# SB_Motor_Driver_Module.net
KiCad netlist of a schematic drawn in Altium Designer
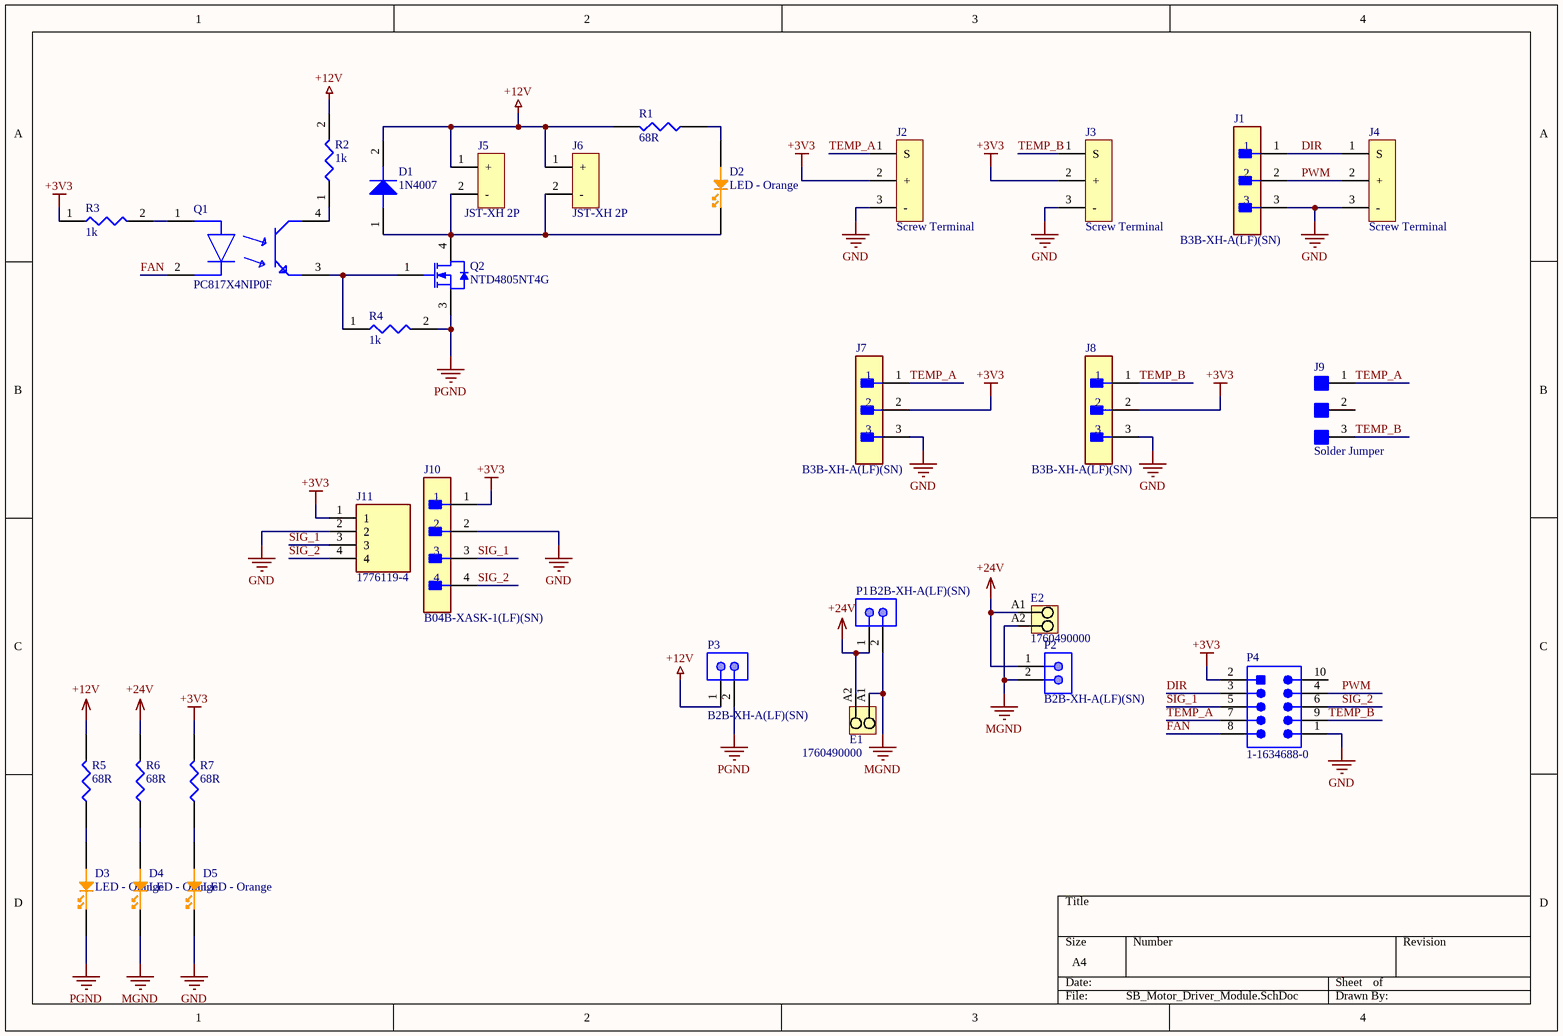
[diagram p0: SB_Motor_Driver_Module.SchDoc]

(export (version "E")
  (design (tool "Eeschema 10.0.6"))
  (components
    (comp (ref "D1")
      (value "1N4007")
      (footprint "M7 1N4007 SMA")
      (description "1000V 1A Rectifier")
      (fields
        (field (name "MANUFACTURER") "Sangdest Microelectronics")
        (field (name "MANUFACTURER PART NUMBER") "1N4007FLTR")
      )
      (libsource (lib "SectionE_BreakOut") (part "1N4007FLTR"))
    )
    (comp (ref "D2")
      (value "LED - Orange")
      (footprint "LED0603-Orange")
      (description "LED ORANGE CLEAR SMD")
      (fields
        (field (name "MANUFACTURER") "Vishay Lite-On")
        (field (name "MANUFACTURER PART NUMBER") "LTST-C191KFKT")
      )
      (libsource (lib "SectionE_BreakOut") (part "LTST-C191KFKT"))
    )
    (comp (ref "D3")
      (value "LED - Orange")
      (footprint "LED0603-Orange")
      (description "LED ORANGE CLEAR SMD")
      (fields
        (field (name "MANUFACTURER") "Vishay Lite-On")
        (field (name "MANUFACTURER PART NUMBER") "LTST-C191KFKT")
      )
      (libsource (lib "SectionE_BreakOut") (part "LTST-C191KFKT"))
    )
    (comp (ref "D4")
      (value "LED - Orange")
      (footprint "LED0603-Orange")
      (description "LED ORANGE CLEAR SMD")
      (fields
        (field (name "MANUFACTURER") "Vishay Lite-On")
        (field (name "MANUFACTURER PART NUMBER") "LTST-C191KFKT")
      )
      (libsource (lib "SectionE_BreakOut") (part "LTST-C191KFKT"))
    )
    (comp (ref "D5")
      (value "LED - Orange")
      (footprint "LED0603-Orange")
      (description "LED ORANGE CLEAR SMD")
      (fields
        (field (name "MANUFACTURER") "Vishay Lite-On")
        (field (name "MANUFACTURER PART NUMBER") "LTST-C191KFKT")
      )
      (libsource (lib "SectionE_BreakOut") (part "LTST-C191KFKT"))
    )
    (comp (ref "E1")
      (value "1760490000")
      (footprint "PM_5_08_90_02")
      (description "OMNIMATE Signal - series PM")
      (fields (field (name "MANUFACTURER") "Weidmueller"))
      (libsource (lib "") (part "Terminal_02_1x02_1"))
    )
    (comp (ref "E2")
      (value "1760490000")
      (footprint "PM_5_08_90_02")
      (description "OMNIMATE Signal - series PM")
      (fields (field (name "MANUFACTURER") "Weidmueller"))
      (libsource (lib "Altium Content Vault") (part "Terminal_02_1x02"))
    )
    (comp (ref "J1")
      (value "B3B-XH-A(LF)(SN)")
      (footprint "FP-B3B-XH-A_LF_SN-MFG")
      (description "CONN HEADER VERT 3POS 2.5MM")
      (fields
        (field (name "OCTOPART") "https://octopart.com/b3b-xh-a%28lf%29%28sn%29-jst-3990185")
        (field (name "MANUFACTURER") "JST")
      )
      (libsource (lib "Altium Content Vault") (part "0d3f023dd272f625e17a2be33dea85f"))
    )
    (comp (ref "J2")
      (value "Screw Terminal")
      (footprint "Screw Terminal 3P 5.08MM")
      (description "TERM BLK 3P SIDE ENT 5.08MM PCB")
      (fields
        (field (name "MANUFACTURER") "On-Shore Technology")
        (field (name "MANUFACTURER PART NUMBER") "OSTTC032162")
      )
      (libsource (lib "SectionE_BreakOut") (part "OSTTC032162"))
    )
    (comp (ref "J3")
      (value "Screw Terminal")
      (footprint "Screw Terminal 3P 5.08MM")
      (description "TERM BLK 3P SIDE ENT 5.08MM PCB")
      (fields
        (field (name "MANUFACTURER") "On-Shore Technology")
        (field (name "MANUFACTURER PART NUMBER") "OSTTC032162")
      )
      (libsource (lib "SectionE_BreakOut") (part "OSTTC032162"))
    )
    (comp (ref "J4")
      (value "Screw Terminal")
      (footprint "Screw Terminal 3P 5.08MM")
      (description "TERM BLK 3P SIDE ENT 5.08MM PCB")
      (fields
        (field (name "MANUFACTURER") "On-Shore Technology")
        (field (name "MANUFACTURER PART NUMBER") "OSTTC032162")
      )
      (libsource (lib "SectionE_BreakOut") (part "OSTTC032162"))
    )
    (comp (ref "J5")
      (value "JST-XH 2P")
      (footprint "JST-XH 2P")
      (description "JST-XH 2 POS 2.5mm Solder ST Thru-Hole Box")
      (fields
        (field (name "MANUFACTURER") "JST")
        (field (name "MANUFACTURER PART NUMBER") "B2B-XH-A(LF)(SN)")
      )
      (libsource (lib "SectionE_BreakOut") (part "B2B-XH-A(LF)(SN)"))
    )
    (comp (ref "J6")
      (value "JST-XH 2P")
      (footprint "JST-XH 2P")
      (description "JST-XH 2 POS 2.5mm Solder ST Thru-Hole Box")
      (fields
        (field (name "MANUFACTURER") "JST")
        (field (name "MANUFACTURER PART NUMBER") "B2B-XH-A(LF)(SN)")
      )
      (libsource (lib "SectionE_BreakOut") (part "B2B-XH-A(LF)(SN)"))
    )
    (comp (ref "J7")
      (value "B3B-XH-A(LF)(SN)")
      (footprint "FP-B3B-XH-A_LF_SN-MFG")
      (description "CONN HEADER VERT 3POS 2.5MM")
      (fields
        (field (name "OCTOPART") "https://octopart.com/b3b-xh-a%28lf%29%28sn%29-jst-3990185")
        (field (name "MANUFACTURER") "JST")
      )
      (libsource (lib "Altium Content Vault") (part "0d3f023dd272f625e17a2be33dea85f"))
    )
    (comp (ref "J8")
      (value "B3B-XH-A(LF)(SN)")
      (footprint "FP-B3B-XH-A_LF_SN-MFG")
      (description "CONN HEADER VERT 3POS 2.5MM")
      (fields
        (field (name "OCTOPART") "https://octopart.com/b3b-xh-a%28lf%29%28sn%29-jst-3990185")
        (field (name "MANUFACTURER") "JST")
      )
      (libsource (lib "Altium Content Vault") (part "0d3f023dd272f625e17a2be33dea85f"))
    )
    (comp (ref "J9")
      (value "Solder Jumper")
      (footprint "Solder Jumper")
      (libsource (lib "SectionE_BreakOut") (part "Solder Jumper"))
    )
    (comp (ref "J10")
      (value "B04B-XASK-1(LF)(SN)")
      (footprint "FP-B04B-XASK-1_LF_SN-MFG")
      (description "CONN HEADER VERT 4POS 2.5MM")
      (fields
        (field (name "OCTOPART") "https://octopart.com/b04b-xask-1%28lf%29%28sn%29-jst-3990149")
        (field (name "MANUFACTURER") "JST")
      )
      (libsource (lib "Altium Content Vault") (part "299a8cea1bdcbc3624fe62c390fa72c"))
    )
    (comp (ref "J11")
      (value "1776119-4")
      (footprint "TE_1776119-4")
      (description "4P TERMI-BLOK,PCB,HIGH TEMP")
      (fields (field (name "MF") "TE Connectivity"))
      (libsource (lib "1776119-4") (part "1776119-4"))
    )
    (comp (ref "P1")
      (value "B2B-XH-A(LF)(SN)")
      (footprint "JST-B2B-XH-A_V")
      (fields (field (name "MANUFACTURER") "JST"))
      (libsource (lib "Altium Content Vault") (part "CN-1P-M-R2"))
    )
    (comp (ref "P2")
      (value "B2B-XH-A(LF)(SN)")
      (footprint "JST-B2B-XH-A_V")
      (fields (field (name "MANUFACTURER") "JST"))
      (libsource (lib "") (part "CN-1P-M-R2_1"))
    )
    (comp (ref "P3")
      (value "B2B-XH-A(LF)(SN)")
      (footprint "JST-B2B-XH-A_V")
      (fields (field (name "MANUFACTURER") "JST"))
      (libsource (lib "Altium Content Vault") (part "CN-1P-M-R2"))
    )
    (comp (ref "P4")
      (value "1-1634688-0")
      (footprint "TECO-1-1634688-0-10_V")
      (fields (field (name "MANUFACTURER") "TE Connectivity"))
      (libsource (lib "Altium Content Vault") (part "CN-2P-M-R10"))
    )
    (comp (ref "Q1")
      (value "PC817X4NIP0F")
      (footprint "FP-PC817X4NIP0F-MFG")
      (description "OPTOISOLATOR 5KV TRANS 4SMD")
      (fields
        (field (name "OCTOPART") "https://octopart.com/pc817x4nip0f-sharp-20650453")
        (field (name "MANUFACTURER") "Sharp")
      )
      (libsource (lib "Altium Content Vault") (part "8ff5844b63c0dea0057760e9ee25456"))
    )
    (comp (ref "Q2")
      (value "NTD4805NT4G")
      (footprint "ONSC-DPAK-3-369AA-01_V")
      (description "Power MOSFET, 30 V, 88 A, Single N-Channel, 3-Pin DPAK, Pb-Free, Tape and Reel")
      (fields (field (name "MANUFACTURER") "On Semiconductor"))
      (libsource (lib "Altium Content Vault") (part "ONSC-NMOS-G1S3D4-3_B"))
    )
    (comp (ref "R1")
      (value "68R")
      (footprint "68R 0603")
      (description "CRGP 0603 68R 1%")
      (fields
        (field (name "MANUFACTURER") "TE Connectivity")
        (field (name "MANUFACTURER PART NUMBER") "CRGP0603F68R")
      )
      (libsource (lib "SectionE_BreakOut") (part "CRGP0603F68R"))
    )
    (comp (ref "R2")
      (value "1k")
      (footprint "R0603 1k")
      (description "0603 1k Ohm 1% 1/10W")
      (fields
        (field (name "MANUFACTURER") "TE Connectivity")
        (field (name "MANUFACTURER PART NUMBER") "CRGCQ0603F1K0")
      )
      (libsource (lib "SectionE_BreakOut") (part "CRGCQ0603F1K0"))
    )
    (comp (ref "R3")
      (value "1k")
      (footprint "R0603 1k")
      (description "0603 1k Ohm 1% 1/10W")
      (fields
        (field (name "MANUFACTURER") "TE Connectivity")
        (field (name "MANUFACTURER PART NUMBER") "CRGCQ0603F1K0")
      )
      (libsource (lib "SectionE_BreakOut") (part "CRGCQ0603F1K0"))
    )
    (comp (ref "R4")
      (value "1k")
      (footprint "R0603 1k")
      (description "0603 1k Ohm 1% 1/10W")
      (fields
        (field (name "MANUFACTURER") "TE Connectivity")
        (field (name "MANUFACTURER PART NUMBER") "CRGCQ0603F1K0")
      )
      (libsource (lib "SectionE_BreakOut") (part "CRGCQ0603F1K0"))
    )
    (comp (ref "R5")
      (value "68R")
      (footprint "68R 0603")
      (description "CRGP 0603 68R 1%")
      (fields
        (field (name "MANUFACTURER") "TE Connectivity")
        (field (name "MANUFACTURER PART NUMBER") "CRGP0603F68R")
      )
      (libsource (lib "SectionE_BreakOut") (part "CRGP0603F68R"))
    )
    (comp (ref "R6")
      (value "68R")
      (footprint "68R 0603")
      (description "CRGP 0603 68R 1%")
      (fields
        (field (name "MANUFACTURER") "TE Connectivity")
        (field (name "MANUFACTURER PART NUMBER") "CRGP0603F68R")
      )
      (libsource (lib "SectionE_BreakOut") (part "CRGP0603F68R"))
    )
    (comp (ref "R7")
      (value "68R")
      (footprint "68R 0603")
      (description "CRGP 0603 68R 1%")
      (fields
        (field (name "MANUFACTURER") "TE Connectivity")
        (field (name "MANUFACTURER PART NUMBER") "CRGP0603F68R")
      )
      (libsource (lib "SectionE_BreakOut") (part "CRGP0603F68R"))
    )
  )
  (nets
    (net (code "1") (name "+3V3") (class "Default")
      (node (ref "J10") (pin "1") (pinfunction "1_1") (pintype "passive"))
      (node (ref "J11") (pin "1") (pinfunction "1_1") (pintype "passive"))
      (node (ref "J2") (pin "2") (pinfunction "+_2") (pintype "passive"))
      (node (ref "J3") (pin "2") (pinfunction "+_2") (pintype "passive"))
      (node (ref "J7") (pin "2") (pinfunction "2_2") (pintype "passive"))
      (node (ref "J8") (pin "2") (pinfunction "2_2") (pintype "passive"))
      (node (ref "P4") (pin "2") (pinfunction "2_2") (pintype "passive"))
      (node (ref "R3") (pin "1") (pinfunction "1_1") (pintype "passive"))
      (node (ref "R7") (pin "2") (pinfunction "2_2") (pintype "passive"))
    )
    (net (code "2") (name "+12V") (class "Default")
      (node (ref "D1") (pin "2") (pinfunction "Cathode_2") (pintype "passive"))
      (node (ref "J5") (pin "1") (pinfunction "+_1") (pintype "passive"))
      (node (ref "J6") (pin "1") (pinfunction "+_1") (pintype "passive"))
      (node (ref "P3") (pin "1") (pinfunction "1_1") (pintype "passive"))
      (node (ref "R1") (pin "2") (pinfunction "2_2") (pintype "passive"))
      (node (ref "R2") (pin "2") (pinfunction "2_2") (pintype "passive"))
      (node (ref "R5") (pin "2") (pinfunction "2_2") (pintype "passive"))
    )
    (net (code "3") (name "+24V") (class "Default")
      (node (ref "E1") (pin "A2") (pinfunction "A2_A2") (pintype "passive"))
      (node (ref "E2") (pin "A1") (pinfunction "A1_A1") (pintype "passive"))
      (node (ref "P1") (pin "1") (pinfunction "1_1") (pintype "passive"))
      (node (ref "P2") (pin "1") (pinfunction "1_1") (pintype "passive"))
      (node (ref "R6") (pin "2") (pinfunction "2_2") (pintype "passive"))
    )
    (net (code "4") (name "/DIR") (class "Default")
      (node (ref "J1") (pin "1") (pinfunction "1_1") (pintype "passive"))
      (node (ref "J4") (pin "1") (pinfunction "S_1") (pintype "passive"))
      (node (ref "P4") (pin "3") (pinfunction "3_3") (pintype "passive"))
    )
    (net (code "5") (name "/FAN") (class "Default")
      (node (ref "P4") (pin "8") (pinfunction "8_8") (pintype "passive"))
      (node (ref "Q1") (pin "2") (pinfunction "C_2") (pintype "passive"))
    )
    (net (code "6") (name "/PWM") (class "Default")
      (node (ref "J1") (pin "2") (pinfunction "2_2") (pintype "passive"))
      (node (ref "J4") (pin "2") (pinfunction "+_2") (pintype "passive"))
      (node (ref "P4") (pin "4") (pinfunction "4_4") (pintype "passive"))
    )
    (net (code "7") (name "/SIG_1") (class "Default")
      (node (ref "J10") (pin "3") (pinfunction "3_3") (pintype "passive"))
      (node (ref "J11") (pin "3") (pinfunction "3_3") (pintype "passive"))
      (node (ref "P4") (pin "5") (pinfunction "5_5") (pintype "passive"))
    )
    (net (code "8") (name "/SIG_2") (class "Default")
      (node (ref "J10") (pin "4") (pinfunction "4_4") (pintype "passive"))
      (node (ref "J11") (pin "4") (pinfunction "4_4") (pintype "passive"))
      (node (ref "P4") (pin "6") (pinfunction "6_6") (pintype "passive"))
    )
    (net (code "9") (name "/TEMP_A") (class "Default")
      (node (ref "J2") (pin "1") (pinfunction "S_1") (pintype "passive"))
      (node (ref "J7") (pin "1") (pinfunction "1_1") (pintype "passive"))
      (node (ref "J9") (pin "1") (pinfunction "1_1") (pintype "passive"))
      (node (ref "P4") (pin "7") (pinfunction "7_7") (pintype "passive"))
    )
    (net (code "10") (name "/TEMP_B") (class "Default")
      (node (ref "J3") (pin "1") (pinfunction "S_1") (pintype "passive"))
      (node (ref "J8") (pin "1") (pinfunction "1_1") (pintype "passive"))
      (node (ref "J9") (pin "3") (pinfunction "3_3") (pintype "passive"))
      (node (ref "P4") (pin "9") (pinfunction "9_9") (pintype "passive"))
    )
    (net (code "11") (name "GND") (class "Default")
      (node (ref "D5") (pin "1") (pinfunction "Cathode_1") (pintype "passive"))
      (node (ref "J1") (pin "3") (pinfunction "3_3") (pintype "passive"))
      (node (ref "J10") (pin "2") (pinfunction "2_2") (pintype "passive"))
      (node (ref "J11") (pin "2") (pinfunction "2_2") (pintype "passive"))
      (node (ref "J2") (pin "3") (pinfunction "-_3") (pintype "passive"))
      (node (ref "J3") (pin "3") (pinfunction "-_3") (pintype "passive"))
      (node (ref "J4") (pin "3") (pinfunction "-_3") (pintype "passive"))
      (node (ref "J7") (pin "3") (pinfunction "3_3") (pintype "passive"))
      (node (ref "J8") (pin "3") (pinfunction "3_3") (pintype "passive"))
      (node (ref "P4") (pin "1") (pinfunction "1_1") (pintype "passive"))
    )
    (net (code "12") (name "MGND") (class "Default")
      (node (ref "D4") (pin "1") (pinfunction "Cathode_1") (pintype "passive"))
      (node (ref "E1") (pin "A1") (pinfunction "A1_A1") (pintype "passive"))
      (node (ref "E2") (pin "A2") (pinfunction "A2_A2") (pintype "passive"))
      (node (ref "P1") (pin "2") (pinfunction "2_2") (pintype "passive"))
      (node (ref "P2") (pin "2") (pinfunction "2_2") (pintype "passive"))
    )
    (net (code "13") (name "Net-(D1-Anode)") (class "Default")
      (node (ref "D1") (pin "1") (pinfunction "Anode_1") (pintype "passive"))
      (node (ref "D2") (pin "1") (pinfunction "Cathode_1") (pintype "passive"))
      (node (ref "J5") (pin "2") (pinfunction "-_2") (pintype "passive"))
      (node (ref "J6") (pin "2") (pinfunction "-_2") (pintype "passive"))
      (node (ref "Q2") (pin "4") (pinfunction "D_4") (pintype "passive"))
    )
    (net (code "14") (name "Net-(D2-Anode)") (class "Default")
      (node (ref "D2") (pin "2") (pinfunction "Anode_2") (pintype "passive"))
      (node (ref "R1") (pin "1") (pinfunction "1_1") (pintype "passive"))
    )
    (net (code "15") (name "Net-(D3-Anode)") (class "Default")
      (node (ref "D3") (pin "2") (pinfunction "Anode_2") (pintype "passive"))
      (node (ref "R5") (pin "1") (pinfunction "1_1") (pintype "passive"))
    )
    (net (code "16") (name "Net-(D4-Anode)") (class "Default")
      (node (ref "D4") (pin "2") (pinfunction "Anode_2") (pintype "passive"))
      (node (ref "R6") (pin "1") (pinfunction "1_1") (pintype "passive"))
    )
    (net (code "17") (name "Net-(D5-Anode)") (class "Default")
      (node (ref "D5") (pin "2") (pinfunction "Anode_2") (pintype "passive"))
      (node (ref "R7") (pin "1") (pinfunction "1_1") (pintype "passive"))
    )
    (net (code "18") (name "Net-(Q1-A)") (class "Default")
      (node (ref "Q1") (pin "1") (pinfunction "A_1") (pintype "passive"))
      (node (ref "R3") (pin "2") (pinfunction "2_2") (pintype "passive"))
    )
    (net (code "19") (name "Net-(Q1-C-Pad4)") (class "Default")
      (node (ref "Q1") (pin "4") (pinfunction "C_4") (pintype "passive"))
      (node (ref "R2") (pin "1") (pinfunction "1_1") (pintype "passive"))
    )
    (net (code "20") (name "Net-(Q1-E)") (class "Default")
      (node (ref "Q1") (pin "3") (pinfunction "E_3") (pintype "passive"))
      (node (ref "Q2") (pin "1") (pinfunction "G_1") (pintype "passive"))
      (node (ref "R4") (pin "1") (pinfunction "1_1") (pintype "passive"))
    )
    (net (code "21") (name "PGND") (class "Default")
      (node (ref "D3") (pin "1") (pinfunction "Cathode_1") (pintype "passive"))
      (node (ref "P3") (pin "2") (pinfunction "2_2") (pintype "passive"))
      (node (ref "Q2") (pin "3") (pinfunction "S_3") (pintype "passive"))
      (node (ref "R4") (pin "2") (pinfunction "2_2") (pintype "passive"))
    )
    (net (code "22") (name "unconnected-(J9-Pad2)") (class "Default")
      (node (ref "J9") (pin "2") (pinfunction "2_2") (pintype "passive"))
    )
    (net (code "23") (name "unconnected-(P4-Pad10)") (class "Default")
      (node (ref "P4") (pin "10") (pinfunction "10_10") (pintype "passive"))
    )
  )
)
